# Converter.net
KiCad netlist of a schematic drawn in Altium Designer
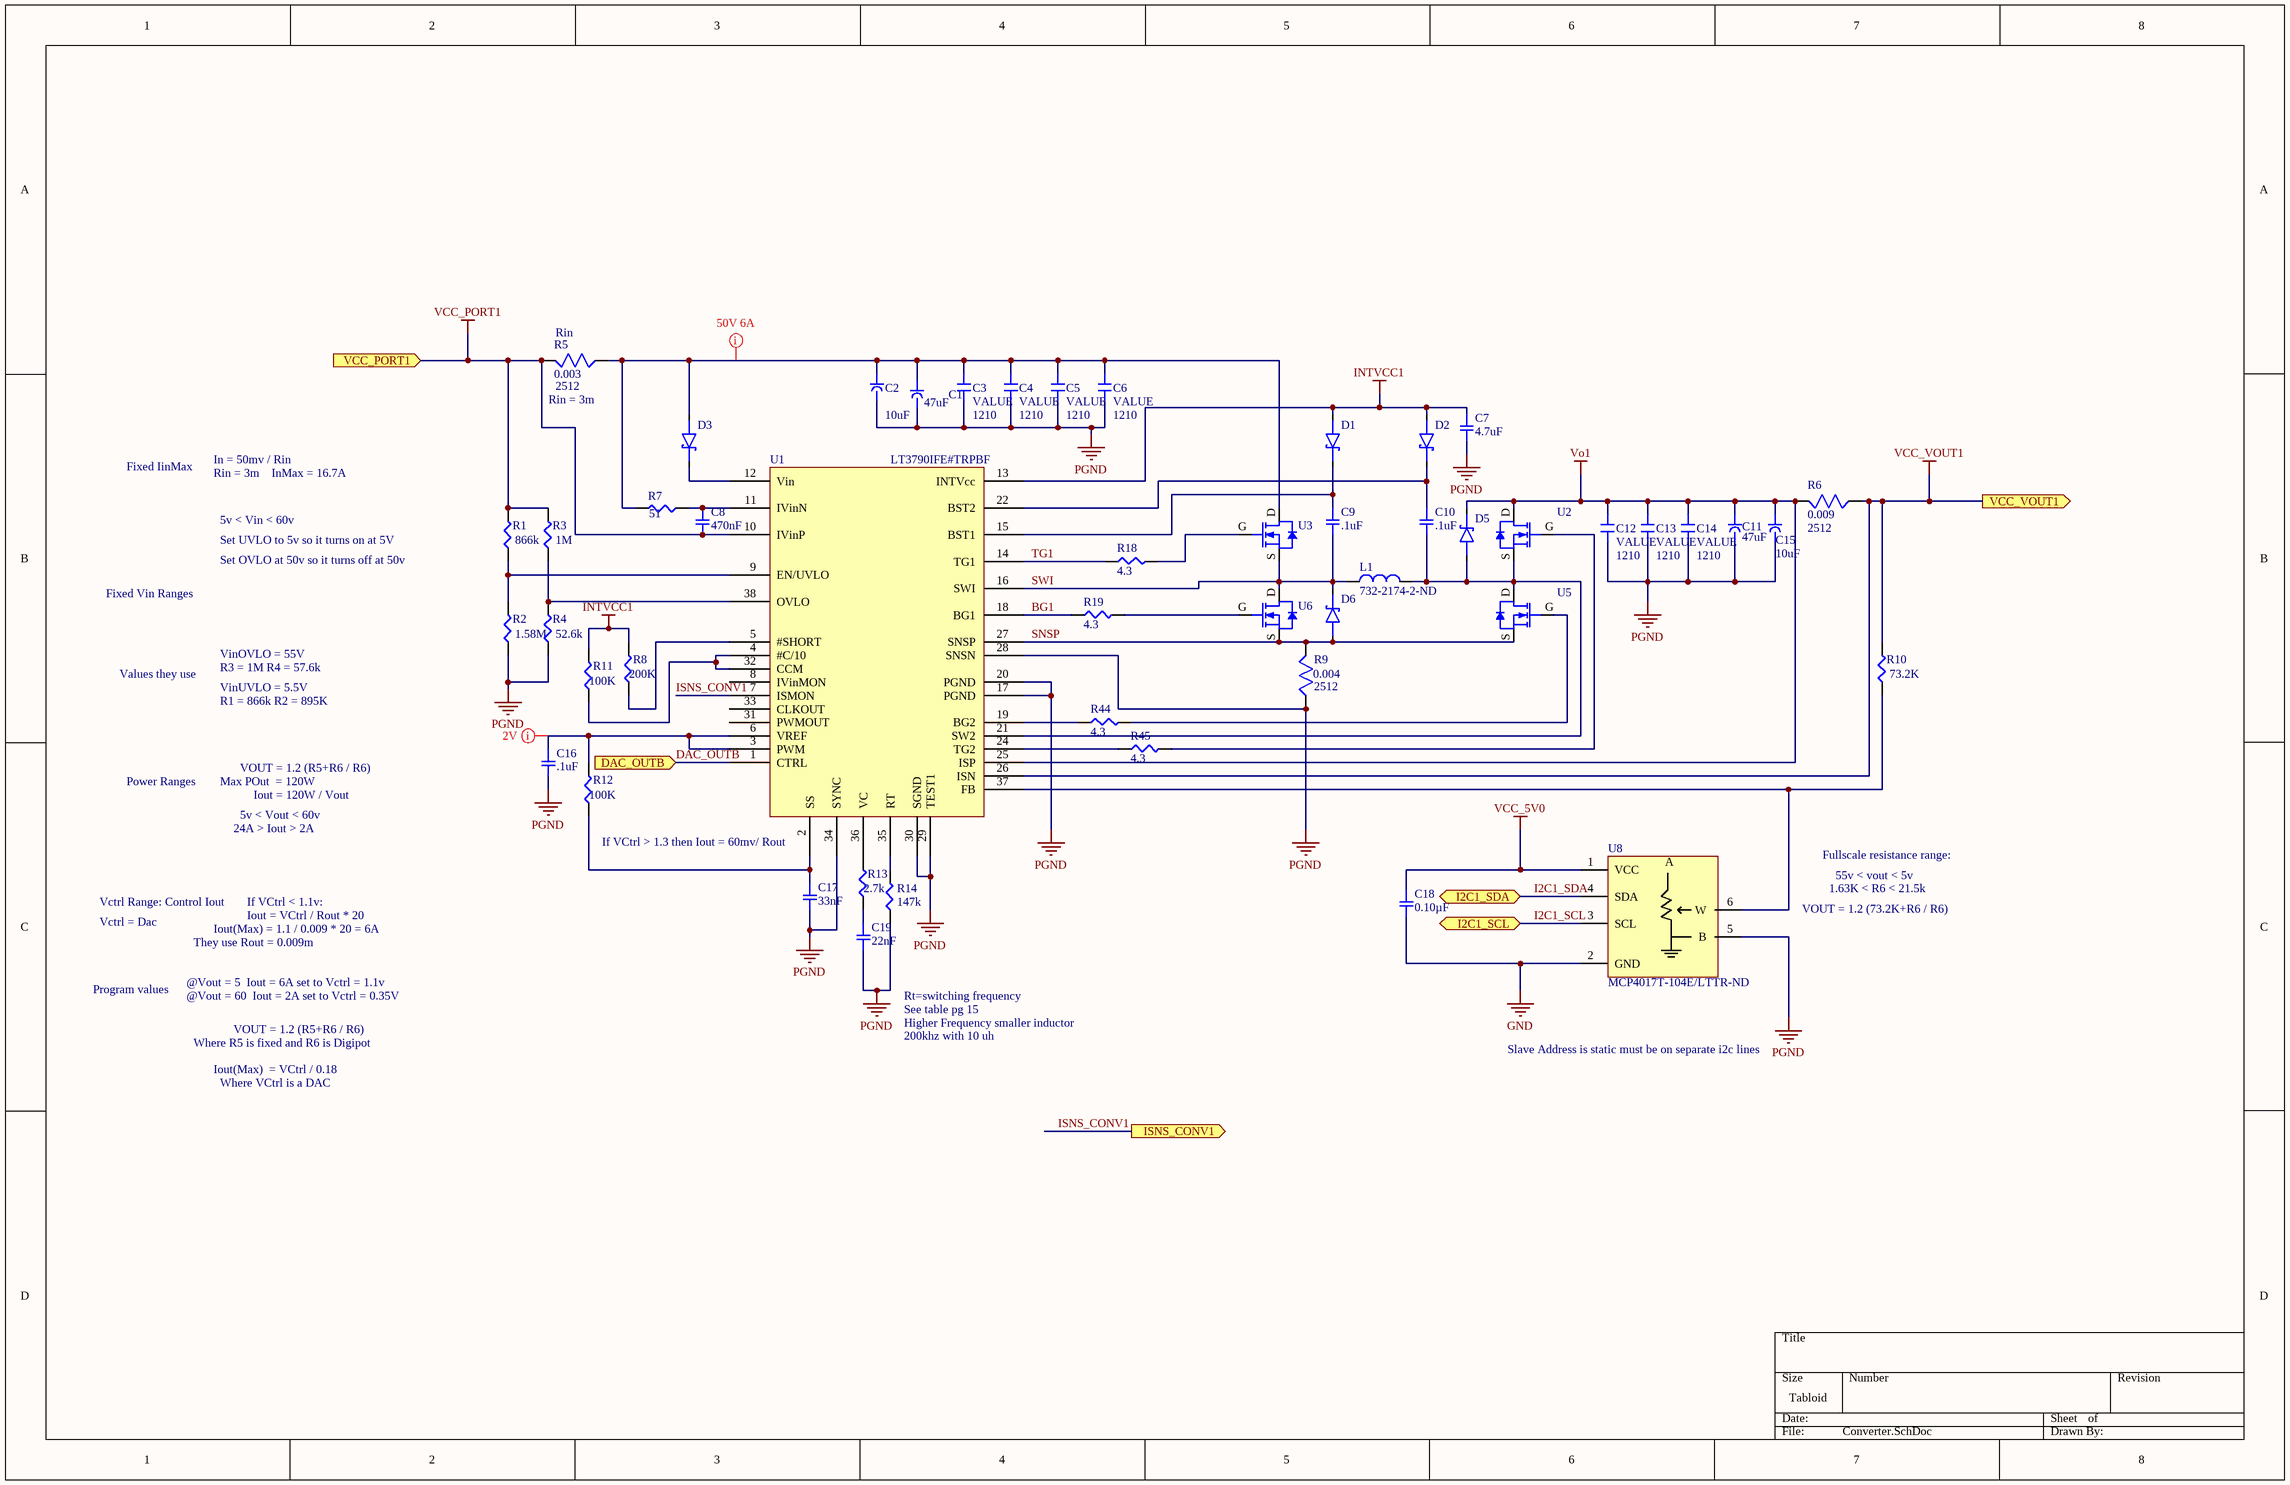
[diagram p0: Converter.SchDoc]

(export (version "E")
  (design (tool "Eeschema 10.0.6"))
  (components
    (comp (ref "C1")
      (value "10-EEE-FN1K470UVTR-ND")
      (footprint "EEE-FN1K470UV")
      (description "CAP ALUM 47UF 20% 80V SMD")
      (libsource (lib "UniversalConverter_Symbols") (part "CAP ALUM 47UF"))
    )
    (comp (ref "C2")
      (value "10uF")
      (footprint "panasonic d8")
      (description "CAP ALUM 10UF 20% 80V SMD")
      (fields (field (name "Comment") "EEE-FN1K100XL"))
      (libsource (lib "UniversalConverter_Symbols") (part "CAP ALUM 10UF"))
    )
    (comp (ref "C3")
      (value "VALUE")
      (footprint "1210 cap")
      (description "CAP SMD 1210")
      (fields (field (name "SIZE") "1210"))
      (libsource (lib "UniversalConverter_Symbols") (part "CAP SMD 1210"))
    )
    (comp (ref "C4")
      (value "VALUE")
      (footprint "1210 cap")
      (description "CAP SMD 1210")
      (fields (field (name "SIZE") "1210"))
      (libsource (lib "UniversalConverter_Symbols") (part "CAP SMD 1210"))
    )
    (comp (ref "C5")
      (value "VALUE")
      (footprint "1210 cap")
      (description "CAP SMD 1210")
      (fields (field (name "SIZE") "1210"))
      (libsource (lib "UniversalConverter_Symbols") (part "CAP SMD 1210"))
    )
    (comp (ref "C6")
      (value "VALUE")
      (footprint "1210 cap")
      (description "CAP SMD 1210")
      (fields (field (name "SIZE") "1210"))
      (libsource (lib "UniversalConverter_Symbols") (part "CAP SMD 1210"))
    )
    (comp (ref "C7")
      (value "4.7uF")
      (footprint "SMD-0603C")
      (description "0603")
      (fields
        (field (name "DIGI-KEY PART NUMBER") "490-5764-1-ND")
        (field (name "PART NUMBER") "GCJ188R71H472KA01D")
      )
      (libsource (lib "capacitor_murata_0603") (part "GCJ188R71H472KA01D"))
    )
    (comp (ref "C8")
      (value "470nF")
      (footprint "SMD-0603C")
      (description "0603")
      (fields
        (field (name "DIGI-KEY PART NUMBER") "490-5764-1-ND")
        (field (name "PART NUMBER") "GCJ188R71H472KA01D")
      )
      (libsource (lib "capacitor_murata_0603") (part "GCJ188R71H472KA01D"))
    )
    (comp (ref "C9")
      (value ".1uF")
      (footprint "SMD-0603C")
      (description "0603")
      (fields
        (field (name "DIGI-KEY PART NUMBER") "490-5764-1-ND")
        (field (name "PART NUMBER") "GCJ188R71H472KA01D")
      )
      (libsource (lib "capacitor_murata_0603") (part "GCJ188R71H472KA01D"))
    )
    (comp (ref "C10")
      (value ".1uF")
      (footprint "SMD-0603C")
      (description "0603")
      (fields
        (field (name "DIGI-KEY PART NUMBER") "490-5764-1-ND")
        (field (name "PART NUMBER") "GCJ188R71H472KA01D")
      )
      (libsource (lib "capacitor_murata_0603") (part "GCJ188R71H472KA01D"))
    )
    (comp (ref "C11")
      (value "10-EEE-FN1K470UVTR-ND")
      (footprint "EEE-FN1K470UV")
      (description "CAP ALUM 47UF 20% 80V SMD")
      (libsource (lib "UniversalConverter_Symbols") (part "CAP ALUM 47UF"))
    )
    (comp (ref "C12")
      (value "VALUE")
      (footprint "1210 cap")
      (description "CAP SMD 1210")
      (fields (field (name "SIZE") "1210"))
      (libsource (lib "UniversalConverter_Symbols") (part "CAP SMD 1210"))
    )
    (comp (ref "C13")
      (value "VALUE")
      (footprint "1210 cap")
      (description "CAP SMD 1210")
      (fields (field (name "SIZE") "1210"))
      (libsource (lib "UniversalConverter_Symbols") (part "CAP SMD 1210"))
    )
    (comp (ref "C14")
      (value "VALUE")
      (footprint "1210 cap")
      (description "CAP SMD 1210")
      (fields (field (name "SIZE") "1210"))
      (libsource (lib "UniversalConverter_Symbols") (part "CAP SMD 1210"))
    )
    (comp (ref "C15")
      (value "10uF")
      (footprint "panasonic d8")
      (description "CAP ALUM 10UF 20% 80V SMD")
      (fields (field (name "Comment") "EEE-FN1K100XL"))
      (libsource (lib "UniversalConverter_Symbols") (part "CAP ALUM 10UF"))
    )
    (comp (ref "C16")
      (value ".1uF")
      (footprint "SMD-0603C")
      (description "0603")
      (fields
        (field (name "DIGI-KEY PART NUMBER") "490-5764-1-ND")
        (field (name "PART NUMBER") "GCJ188R71H472KA01D")
      )
      (libsource (lib "capacitor_murata_0603") (part "GCJ188R71H472KA01D"))
    )
    (comp (ref "C17")
      (value "33nF")
      (footprint "SMD-0603C")
      (description "0603")
      (fields
        (field (name "DIGI-KEY PART NUMBER") "490-5764-1-ND")
        (field (name "PART NUMBER") "GCJ188R71H472KA01D")
      )
      (libsource (lib "capacitor_murata_0603") (part "GCJ188R71H472KA01D"))
    )
    (comp (ref "C18")
      (value "0.10µF")
      (footprint "SMD-0603C")
      (description "CAP CER 0.1UF 50V X7R 0603")
      (fields
        (field (name "DIGI-KEY PART NUMBER") "490-5798-1-ND")
        (field (name "PART NUMBER") "GCJ188R71H104KA12D")
      )
      (libsource (lib "capacitor_murata_0603") (part "GCJ188R71H104KA12D"))
    )
    (comp (ref "C19")
      (value "22nF")
      (footprint "SMD-0603C")
      (description "0603")
      (fields
        (field (name "DIGI-KEY PART NUMBER") "490-5764-1-ND")
        (field (name "PART NUMBER") "GCJ188R71H472KA01D")
      )
      (libsource (lib "capacitor_murata_0603") (part "GCJ188R71H472KA01D"))
    )
    (comp (ref "D1")
      (value "BAT46WJ,115")
      (footprint "SOD323F")
      (description "DIODE SCHOTTKY 100V 250MA SOD323\r\n\r\nDiode Schottky 100 V 250mA (DC) Surface Mount SOD-323F")
      (fields (field (name "COPYRIGHT") "Copyright (C) 2021 Ultra Librarian. All rights reserved."))
      (libsource (lib "UniversalConverter_Symbols") (part "BAT46WJ,115"))
    )
    (comp (ref "D2")
      (value "BAT46WJ,115")
      (footprint "SOD323F")
      (description "DIODE SCHOTTKY 100V 250MA SOD323\r\n\r\nDiode Schottky 100 V 250mA (DC) Surface Mount SOD-323F")
      (fields (field (name "COPYRIGHT") "Copyright (C) 2021 Ultra Librarian. All rights reserved."))
      (libsource (lib "UniversalConverter_Symbols") (part "BAT46WJ,115"))
    )
    (comp (ref "D3")
      (value "SK58L-TPMSTR-ND")
      (footprint "SMC(DO-214AB)")
      (description "DIODE SCHOTTKY 80V 5A DO214AB/SMC\r\n\r\nDiode Schottky 80 V 5A Surface Mount SMC (DO-214AB)")
      (libsource (lib "UniversalConverter_Parts") (part "DIODE SK58L-TP"))
    )
    (comp (ref "D5")
      (value "SK58L-TPMSTR-ND")
      (footprint "SMC(DO-214AB)")
      (description "DIODE SCHOTTKY 80V 5A DO214AB/SMC\r\n\r\nDiode Schottky 80 V 5A Surface Mount SMC (DO-214AB)")
      (libsource (lib "UniversalConverter_Parts") (part "DIODE SK58L-TP"))
    )
    (comp (ref "D6")
      (value "SK58L-TPMSTR-ND")
      (footprint "SMC(DO-214AB)")
      (description "DIODE SCHOTTKY 80V 5A DO214AB/SMC\r\n\r\nDiode Schottky 80 V 5A Surface Mount SMC (DO-214AB)")
      (libsource (lib "UniversalConverter_Parts") (part "DIODE SK58L-TP"))
    )
    (comp (ref "L1")
      (value "732-2174-2-ND")
      (footprint "Inductor")
      (description "FIXED IND 6.8UH 18.5A 4.1MOHM SM")
      (libsource (lib "UniversalConverter_Parts") (part "INDUCTOR 7443556680"))
    )
    (comp (ref "R1")
      (value "866k")
      (footprint "SMD-0603-RES")
      (description "0603")
      (fields (field (name "PART NUMBER") "ERJ-3BQJ5R6V") (field (name "DIGI-KEY PART NUMBER") "P17425CT-ND"))
      (libsource (lib "Panasonic_ERJ_0603") (part "ERJ-3BQJ5R6V"))
    )
    (comp (ref "R2")
      (value "1.58M")
      (footprint "SMD-0603-RES")
      (description "0603")
      (fields (field (name "PART NUMBER") "ERJ-3BQJ5R6V") (field (name "DIGI-KEY PART NUMBER") "P17425CT-ND"))
      (libsource (lib "Panasonic_ERJ_0603") (part "ERJ-3BQJ5R6V"))
    )
    (comp (ref "R3")
      (value "1M")
      (footprint "SMD-0603-RES")
      (description "0603")
      (fields (field (name "PART NUMBER") "ERJ-3BQJ5R6V") (field (name "DIGI-KEY PART NUMBER") "P17425CT-ND"))
      (libsource (lib "Panasonic_ERJ_0603") (part "ERJ-3BQJ5R6V"))
    )
    (comp (ref "R4")
      (value "52.6k")
      (footprint "SMD-0603-RES")
      (description "0603")
      (fields (field (name "PART NUMBER") "ERJ-3BQJ5R6V") (field (name "DIGI-KEY PART NUMBER") "P17425CT-ND"))
      (libsource (lib "Panasonic_ERJ_0603") (part "ERJ-3BQJ5R6V"))
    )
    (comp (ref "R5")
      (value "0.003")
      (footprint "2512")
      (description "RES SMD 2512 2W")
      (fields (field (name "SIZE") "2512"))
      (libsource (lib "UniversalConverter_Symbols") (part "RES SMD 2512"))
    )
    (comp (ref "R6")
      (value "0.009")
      (footprint "2512")
      (description "RES SMD 2512 2W")
      (fields (field (name "SIZE") "2512"))
      (libsource (lib "UniversalConverter_Symbols") (part "RES SMD 2512"))
    )
    (comp (ref "R7")
      (value "51")
      (footprint "SMD-0603-RES")
      (description "0603")
      (fields (field (name "PART NUMBER") "ERJ-3BQJ5R6V") (field (name "DIGI-KEY PART NUMBER") "P17425CT-ND"))
      (libsource (lib "Panasonic_ERJ_0603") (part "ERJ-3BQJ5R6V"))
    )
    (comp (ref "R8")
      (value "200K")
      (footprint "SMD-0603-RES")
      (description "0603")
      (fields (field (name "PART NUMBER") "ERJ-3BQJ5R6V") (field (name "DIGI-KEY PART NUMBER") "P17425CT-ND"))
      (libsource (lib "Panasonic_ERJ_0603") (part "ERJ-3BQJ5R6V"))
    )
    (comp (ref "R9")
      (value "0.004")
      (footprint "2512")
      (description "RES SMD 2512 2W")
      (fields (field (name "SIZE") "2512"))
      (libsource (lib "UniversalConverter_Symbols") (part "RES SMD 2512"))
    )
    (comp (ref "R10")
      (value "73.2K")
      (footprint "SMD-0603-RES")
      (description "0603")
      (fields (field (name "PART NUMBER") "ERJ-3BQJ5R6V") (field (name "DIGI-KEY PART NUMBER") "P17425CT-ND"))
      (libsource (lib "Panasonic_ERJ_0603") (part "ERJ-3BQJ5R6V"))
    )
    (comp (ref "R11")
      (value "100K")
      (footprint "SMD-0603-RES")
      (description "0603")
      (fields (field (name "PART NUMBER") "ERJ-3BQJ5R6V") (field (name "DIGI-KEY PART NUMBER") "P17425CT-ND"))
      (libsource (lib "Panasonic_ERJ_0603") (part "ERJ-3BQJ5R6V"))
    )
    (comp (ref "R12")
      (value "100K")
      (footprint "SMD-0603-RES")
      (description "0603")
      (fields (field (name "PART NUMBER") "ERJ-3BQJ5R6V") (field (name "DIGI-KEY PART NUMBER") "P17425CT-ND"))
      (libsource (lib "Panasonic_ERJ_0603") (part "ERJ-3BQJ5R6V"))
    )
    (comp (ref "R13")
      (value "2.7k")
      (footprint "SMD-0603-RES")
      (description "0603")
      (fields (field (name "PART NUMBER") "ERJ-3BQJ5R6V") (field (name "DIGI-KEY PART NUMBER") "P17425CT-ND"))
      (libsource (lib "Panasonic_ERJ_0603") (part "ERJ-3BQJ5R6V"))
    )
    (comp (ref "R14")
      (value "147k")
      (footprint "SMD-0603-RES")
      (description "0603")
      (fields (field (name "PART NUMBER") "ERJ-3BQJ5R6V") (field (name "DIGI-KEY PART NUMBER") "P17425CT-ND"))
      (libsource (lib "Panasonic_ERJ_0603") (part "ERJ-3BQJ5R6V"))
    )
    (comp (ref "R18")
      (value "4.3")
      (footprint "SMD-0603-RES")
      (description "RES SMD 1 OHM 1% 1/4W 0603")
      (fields (field (name "PART NUMBER") "ERJ-3BQF1R0V") (field (name "DIGI-KEY PART NUMBER") "P17371CT-ND"))
      (libsource (lib "Panasonic_ERJ_0603") (part "ERJ-3BQF1R0V"))
    )
    (comp (ref "R19")
      (value "4.3")
      (footprint "SMD-0603-RES")
      (description "RES SMD 1 OHM 1% 1/4W 0603")
      (fields (field (name "PART NUMBER") "ERJ-3BQF1R0V") (field (name "DIGI-KEY PART NUMBER") "P17371CT-ND"))
      (libsource (lib "Panasonic_ERJ_0603") (part "ERJ-3BQF1R0V"))
    )
    (comp (ref "R44")
      (value "4.3")
      (footprint "SMD-0603-RES")
      (description "RES SMD 1 OHM 1% 1/4W 0603")
      (fields (field (name "PART NUMBER") "ERJ-3BQF1R0V") (field (name "DIGI-KEY PART NUMBER") "P17371CT-ND"))
      (libsource (lib "Panasonic_ERJ_0603") (part "ERJ-3BQF1R0V"))
    )
    (comp (ref "R45")
      (value "4.3")
      (footprint "SMD-0603-RES")
      (description "RES SMD 1 OHM 1% 1/4W 0603")
      (fields (field (name "PART NUMBER") "ERJ-3BQF1R0V") (field (name "DIGI-KEY PART NUMBER") "P17371CT-ND"))
      (libsource (lib "Panasonic_ERJ_0603") (part "ERJ-3BQF1R0V"))
    )
    (comp (ref "U1")
      (value "LT3790IFE#TRPBF")
      (footprint "TSSOP-38-GNDPAD")
      (libsource (lib "UniversalConverter_Parts") (part "IC LT3790 BUCK/BOOST 60V 150W"))
    )
    (comp (ref "U2")
      (value "SQJA80EP-T1_GE3TR-ND")
      (footprint "PowerPAK® SO-8L SINGLE")
      (description "MOSFET N-CH 80V 60A PPAK SO-8")
      (libsource (lib "UniversalConverter_Parts") (part "FET SQJA80EP-T1_GE3"))
    )
    (comp (ref "U3")
      (value "SQJA80EP-T1_GE3TR-ND")
      (footprint "PowerPAK® SO-8L SINGLE")
      (description "MOSFET N-CH 80V 60A PPAK SO-8")
      (libsource (lib "UniversalConverter_Parts") (part "FET SQJA80EP-T1_GE3"))
    )
    (comp (ref "U5")
      (value "SQJA80EP-T1_GE3TR-ND")
      (footprint "PowerPAK® SO-8L SINGLE")
      (description "MOSFET N-CH 80V 60A PPAK SO-8")
      (libsource (lib "UniversalConverter_Parts") (part "FET SQJA80EP-T1_GE3"))
    )
    (comp (ref "U6")
      (value "SQJA80EP-T1_GE3TR-ND")
      (footprint "PowerPAK® SO-8L SINGLE")
      (description "MOSFET N-CH 80V 60A PPAK SO-8")
      (libsource (lib "UniversalConverter_Parts") (part "FET SQJA80EP-T1_GE3"))
    )
    (comp (ref "U8")
      (value "MCP4017T-104E/LTTR-ND")
      (footprint "SC70")
      (description "IC DGT POT 100KOHM 128TAP SC70-6")
      (libsource (lib "UniversalConverter_Symbols") (part "IC DIGIPOT MCP4017T-104E/LT"))
    )
  )
  (nets
    (net (code "1") (name "/BG1") (class "Default")
      (node (ref "R19") (pin "1") (pinfunction "1_1") (pintype "passive"))
      (node (ref "U1") (pin "18") (pinfunction "BG1_18") (pintype "passive"))
    )
    (net (code "2") (name "/DAC_OUTB") (class "Default")
      (node (ref "U1") (pin "1") (pinfunction "CTRL_1") (pintype "passive"))
    )
    (net (code "3") (name "/I2C1_SCL") (class "Default")
      (node (ref "U8") (pin "3") (pinfunction "SCL_3") (pintype "passive"))
    )
    (net (code "4") (name "/I2C1_SDA") (class "Default")
      (node (ref "U8") (pin "4") (pinfunction "SDA_4") (pintype "passive"))
    )
    (net (code "5") (name "/ISNS_CONV1") (class "Default")
      (node (ref "U1") (pin "7") (pinfunction "ISMON_7") (pintype "passive"))
    )
    (net (code "6") (name "/SNSP") (class "Default")
      (node (ref "D6") (pin "2") (pinfunction "2_2") (pintype "passive"))
      (node (ref "R9") (pin "2") (pinfunction "2_2") (pintype "passive"))
      (node (ref "U1") (pin "27") (pinfunction "SNSP_27") (pintype "passive"))
      (node (ref "U5") (pin "S") (pinfunction "SOURCE_S") (pintype "passive"))
      (node (ref "U6") (pin "S") (pinfunction "SOURCE_S") (pintype "passive"))
    )
    (net (code "7") (name "/SWI") (class "Default")
      (node (ref "C9") (pin "2") (pinfunction "2_2") (pintype "passive"))
      (node (ref "D6") (pin "1") (pinfunction "1_1") (pintype "passive"))
      (node (ref "L1") (pin "1") (pinfunction "1_1") (pintype "passive"))
      (node (ref "U1") (pin "16") (pinfunction "SWI_16") (pintype "passive"))
      (node (ref "U3") (pin "S") (pinfunction "SOURCE_S") (pintype "passive"))
      (node (ref "U6") (pin "D") (pinfunction "DRAIN_D") (pintype "passive"))
    )
    (net (code "8") (name "/TG1") (class "Default")
      (node (ref "R18") (pin "1") (pinfunction "1_1") (pintype "passive"))
      (node (ref "U1") (pin "14") (pinfunction "TG1_14") (pintype "passive"))
    )
    (net (code "9") (name "GND") (class "Default")
      (node (ref "C18") (pin "2") (pinfunction "2_2") (pintype "passive"))
      (node (ref "U8") (pin "2") (pinfunction "GND_2") (pintype "passive"))
    )
    (net (code "10") (name "INTVCC1") (class "Default")
      (node (ref "C7") (pin "1") (pinfunction "1_1") (pintype "passive"))
      (node (ref "D1") (pin "2") (pinfunction "2_2") (pintype "passive"))
      (node (ref "D2") (pin "2") (pinfunction "2_2") (pintype "passive"))
      (node (ref "R11") (pin "2") (pinfunction "2_2") (pintype "passive"))
      (node (ref "R8") (pin "2") (pinfunction "2_2") (pintype "passive"))
      (node (ref "U1") (pin "13") (pinfunction "INTVcc_13") (pintype "passive"))
    )
    (net (code "11") (name "Net-(C19-Pad1)") (class "Default")
      (node (ref "C19") (pin "1") (pinfunction "1_1") (pintype "passive"))
      (node (ref "R13") (pin "1") (pinfunction "1_1") (pintype "passive"))
    )
    (net (code "12") (name "Net-(U1-#C{slash}10)") (class "Default")
      (node (ref "R11") (pin "1") (pinfunction "1_1") (pintype "passive"))
      (node (ref "U1") (pin "32") (pinfunction "CCM_32") (pintype "passive"))
      (node (ref "U1") (pin "4") (pinfunction "#C/10_4") (pintype "passive"))
    )
    (net (code "13") (name "Net-(U1-#SHORT)") (class "Default")
      (node (ref "R8") (pin "1") (pinfunction "1_1") (pintype "passive"))
      (node (ref "U1") (pin "5") (pinfunction "#SHORT_5") (pintype "passive"))
    )
    (net (code "14") (name "Net-(U1-BG2)") (class "Default")
      (node (ref "R44") (pin "1") (pinfunction "1_1") (pintype "passive"))
      (node (ref "U1") (pin "19") (pinfunction "BG2_19") (pintype "passive"))
    )
    (net (code "15") (name "Net-(U1-BST1)") (class "Default")
      (node (ref "C9") (pin "1") (pinfunction "1_1") (pintype "passive"))
      (node (ref "D1") (pin "1") (pinfunction "1_1") (pintype "passive"))
      (node (ref "U1") (pin "15") (pinfunction "BST1_15") (pintype "passive"))
    )
    (net (code "16") (name "Net-(U1-BST2)") (class "Default")
      (node (ref "C10") (pin "1") (pinfunction "1_1") (pintype "passive"))
      (node (ref "D2") (pin "1") (pinfunction "1_1") (pintype "passive"))
      (node (ref "U1") (pin "22") (pinfunction "BST2_22") (pintype "passive"))
    )
    (net (code "17") (name "Net-(U1-EN{slash}UVLO)") (class "Default")
      (node (ref "R1") (pin "1") (pinfunction "1_1") (pintype "passive"))
      (node (ref "R2") (pin "2") (pinfunction "2_2") (pintype "passive"))
      (node (ref "U1") (pin "9") (pinfunction "EN/UVLO_9") (pintype "passive"))
    )
    (net (code "18") (name "Net-(U1-FB)") (class "Default")
      (node (ref "R10") (pin "1") (pinfunction "1_1") (pintype "passive"))
      (node (ref "U1") (pin "37") (pinfunction "FB_37") (pintype "passive"))
      (node (ref "U8") (pin "6") (pinfunction "W_6") (pintype "passive"))
    )
    (net (code "19") (name "Net-(U1-IVinN)") (class "Default")
      (node (ref "C8") (pin "1") (pinfunction "1_1") (pintype "passive"))
      (node (ref "R7") (pin "1") (pinfunction "1_1") (pintype "passive"))
      (node (ref "U1") (pin "11") (pinfunction "IVinN_11") (pintype "passive"))
    )
    (net (code "20") (name "Net-(U1-OVLO)") (class "Default")
      (node (ref "R3") (pin "1") (pinfunction "1_1") (pintype "passive"))
      (node (ref "R4") (pin "2") (pinfunction "2_2") (pintype "passive"))
      (node (ref "U1") (pin "38") (pinfunction "OVLO_38") (pintype "passive"))
    )
    (net (code "21") (name "Net-(U1-PWM)") (class "Default")
      (node (ref "C16") (pin "1") (pinfunction "1_1") (pintype "passive"))
      (node (ref "R12") (pin "2") (pinfunction "2_2") (pintype "passive"))
      (node (ref "U1") (pin "3") (pinfunction "PWM_3") (pintype "passive"))
      (node (ref "U1") (pin "6") (pinfunction "VREF_6") (pintype "passive"))
    )
    (net (code "22") (name "Net-(U1-RT)") (class "Default")
      (node (ref "R14") (pin "2") (pinfunction "2_2") (pintype "passive"))
      (node (ref "U1") (pin "35") (pinfunction "RT_35") (pintype "passive"))
    )
    (net (code "23") (name "Net-(U1-SS)") (class "Default")
      (node (ref "C17") (pin "1") (pinfunction "1_1") (pintype "passive"))
      (node (ref "R12") (pin "1") (pinfunction "1_1") (pintype "passive"))
      (node (ref "U1") (pin "2") (pinfunction "SS_2") (pintype "passive"))
    )
    (net (code "24") (name "Net-(U1-SW2)") (class "Default")
      (node (ref "C10") (pin "2") (pinfunction "2_2") (pintype "passive"))
      (node (ref "D5") (pin "2") (pinfunction "2_2") (pintype "passive"))
      (node (ref "L1") (pin "2") (pinfunction "2_2") (pintype "passive"))
      (node (ref "U1") (pin "21") (pinfunction "SW2_21") (pintype "passive"))
      (node (ref "U2") (pin "S") (pinfunction "SOURCE_S") (pintype "passive"))
      (node (ref "U5") (pin "D") (pinfunction "DRAIN_D") (pintype "passive"))
    )
    (net (code "25") (name "Net-(U1-TG2)") (class "Default")
      (node (ref "R45") (pin "1") (pinfunction "1_1") (pintype "passive"))
      (node (ref "U1") (pin "24") (pinfunction "TG2_24") (pintype "passive"))
    )
    (net (code "26") (name "Net-(U1-VC)") (class "Default")
      (node (ref "R13") (pin "2") (pinfunction "2_2") (pintype "passive"))
      (node (ref "U1") (pin "36") (pinfunction "VC_36") (pintype "passive"))
    )
    (net (code "27") (name "Net-(U1-Vin)") (class "Default")
      (node (ref "D3") (pin "1") (pinfunction "1_1") (pintype "passive"))
      (node (ref "U1") (pin "12") (pinfunction "Vin_12") (pintype "passive"))
    )
    (net (code "28") (name "Net-(U2-GATE)") (class "Default")
      (node (ref "R45") (pin "2") (pinfunction "2_2") (pintype "passive"))
      (node (ref "U2") (pin "G") (pinfunction "GATE_G") (pintype "passive"))
    )
    (net (code "29") (name "Net-(U3-DRAIN)") (class "Default")
      (node (ref "C1") (pin "2") (pinfunction "2_2") (pintype "passive"))
      (node (ref "C2") (pin "1") (pinfunction "1_1") (pintype "passive"))
      (node (ref "C3") (pin "1") (pinfunction "1_1") (pintype "passive"))
      (node (ref "C4") (pin "1") (pinfunction "1_1") (pintype "passive"))
      (node (ref "C5") (pin "1") (pinfunction "1_1") (pintype "passive"))
      (node (ref "C6") (pin "1") (pinfunction "1_1") (pintype "passive"))
      (node (ref "D3") (pin "2") (pinfunction "2_2") (pintype "passive"))
      (node (ref "R5") (pin "1") (pinfunction "1_1") (pintype "passive"))
      (node (ref "R7") (pin "2") (pinfunction "2_2") (pintype "passive"))
      (node (ref "U3") (pin "D") (pinfunction "DRAIN_D") (pintype "passive"))
    )
    (net (code "30") (name "Net-(U3-GATE)") (class "Default")
      (node (ref "R18") (pin "2") (pinfunction "2_2") (pintype "passive"))
      (node (ref "U3") (pin "G") (pinfunction "GATE_G") (pintype "passive"))
    )
    (net (code "31") (name "Net-(U5-GATE)") (class "Default")
      (node (ref "R44") (pin "2") (pinfunction "2_2") (pintype "passive"))
      (node (ref "U5") (pin "G") (pinfunction "GATE_G") (pintype "passive"))
    )
    (net (code "32") (name "Net-(U6-GATE)") (class "Default")
      (node (ref "R19") (pin "2") (pinfunction "2_2") (pintype "passive"))
      (node (ref "U6") (pin "G") (pinfunction "GATE_G") (pintype "passive"))
    )
    (net (code "33") (name "PGND") (class "Default")
      (node (ref "C1") (pin "1") (pinfunction "1_1") (pintype "passive"))
      (node (ref "C11") (pin "1") (pinfunction "1_1") (pintype "passive"))
      (node (ref "C12") (pin "2") (pinfunction "2_2") (pintype "passive"))
      (node (ref "C13") (pin "2") (pinfunction "2_2") (pintype "passive"))
      (node (ref "C14") (pin "2") (pinfunction "2_2") (pintype "passive"))
      (node (ref "C15") (pin "2") (pinfunction "2_2") (pintype "passive"))
      (node (ref "C16") (pin "2") (pinfunction "2_2") (pintype "passive"))
      (node (ref "C17") (pin "2") (pinfunction "2_2") (pintype "passive"))
      (node (ref "C19") (pin "2") (pinfunction "2_2") (pintype "passive"))
      (node (ref "C2") (pin "2") (pinfunction "2_2") (pintype "passive"))
      (node (ref "C3") (pin "2") (pinfunction "2_2") (pintype "passive"))
      (node (ref "C4") (pin "2") (pinfunction "2_2") (pintype "passive"))
      (node (ref "C5") (pin "2") (pinfunction "2_2") (pintype "passive"))
      (node (ref "C6") (pin "2") (pinfunction "2_2") (pintype "passive"))
      (node (ref "C7") (pin "2") (pinfunction "2_2") (pintype "passive"))
      (node (ref "R14") (pin "1") (pinfunction "1_1") (pintype "passive"))
      (node (ref "R2") (pin "1") (pinfunction "1_1") (pintype "passive"))
      (node (ref "R4") (pin "1") (pinfunction "1_1") (pintype "passive"))
      (node (ref "R9") (pin "1") (pinfunction "1_1") (pintype "passive"))
      (node (ref "U1") (pin "17") (pinfunction "PGND_17") (pintype "passive"))
      (node (ref "U1") (pin "20") (pinfunction "PGND_20") (pintype "passive"))
      (node (ref "U1") (pin "28") (pinfunction "SNSN_28") (pintype "passive"))
      (node (ref "U1") (pin "29") (pinfunction "TEST1_29") (pintype "passive"))
      (node (ref "U1") (pin "30") (pinfunction "SGND_30") (pintype "passive"))
      (node (ref "U1") (pin "34") (pinfunction "SYNC_34") (pintype "passive"))
      (node (ref "U8") (pin "5") (pinfunction "B_5") (pintype "passive"))
    )
    (net (code "34") (name "VCC_5V0") (class "Default")
      (node (ref "C18") (pin "1") (pinfunction "1_1") (pintype "passive"))
      (node (ref "U8") (pin "1") (pinfunction "VCC_1") (pintype "passive"))
    )
    (net (code "35") (name "VCC_PORT1") (class "Default")
      (node (ref "C8") (pin "2") (pinfunction "2_2") (pintype "passive"))
      (node (ref "R1") (pin "2") (pinfunction "2_2") (pintype "passive"))
      (node (ref "R3") (pin "2") (pinfunction "2_2") (pintype "passive"))
      (node (ref "R5") (pin "2") (pinfunction "2_2") (pintype "passive"))
      (node (ref "U1") (pin "10") (pinfunction "IVinP_10") (pintype "passive"))
    )
    (net (code "36") (name "VCC_VOUT1") (class "Default")
      (node (ref "R10") (pin "2") (pinfunction "2_2") (pintype "passive"))
      (node (ref "R6") (pin "1") (pinfunction "1_1") (pintype "passive"))
      (node (ref "U1") (pin "26") (pinfunction "ISN_26") (pintype "passive"))
    )
    (net (code "37") (name "Vo1") (class "Default")
      (node (ref "C11") (pin "2") (pinfunction "2_2") (pintype "passive"))
      (node (ref "C12") (pin "1") (pinfunction "1_1") (pintype "passive"))
      (node (ref "C13") (pin "1") (pinfunction "1_1") (pintype "passive"))
      (node (ref "C14") (pin "1") (pinfunction "1_1") (pintype "passive"))
      (node (ref "C15") (pin "1") (pinfunction "1_1") (pintype "passive"))
      (node (ref "D5") (pin "1") (pinfunction "1_1") (pintype "passive"))
      (node (ref "R6") (pin "2") (pinfunction "2_2") (pintype "passive"))
      (node (ref "U1") (pin "25") (pinfunction "ISP_25") (pintype "passive"))
      (node (ref "U2") (pin "D") (pinfunction "DRAIN_D") (pintype "passive"))
    )
    (net (code "38") (name "unconnected-(U1-CLKOUT-Pad33)") (class "Default")
      (node (ref "U1") (pin "33") (pinfunction "CLKOUT_33") (pintype "passive"))
    )
    (net (code "39") (name "unconnected-(U1-IVinMON-Pad8)") (class "Default")
      (node (ref "U1") (pin "8") (pinfunction "IVinMON_8") (pintype "passive"))
    )
    (net (code "40") (name "unconnected-(U1-PWMOUT-Pad31)") (class "Default")
      (node (ref "U1") (pin "31") (pinfunction "PWMOUT_31") (pintype "passive"))
    )
  )
)
